# fm-radio.net
KiCad netlist of a schematic drawn in EAGLE
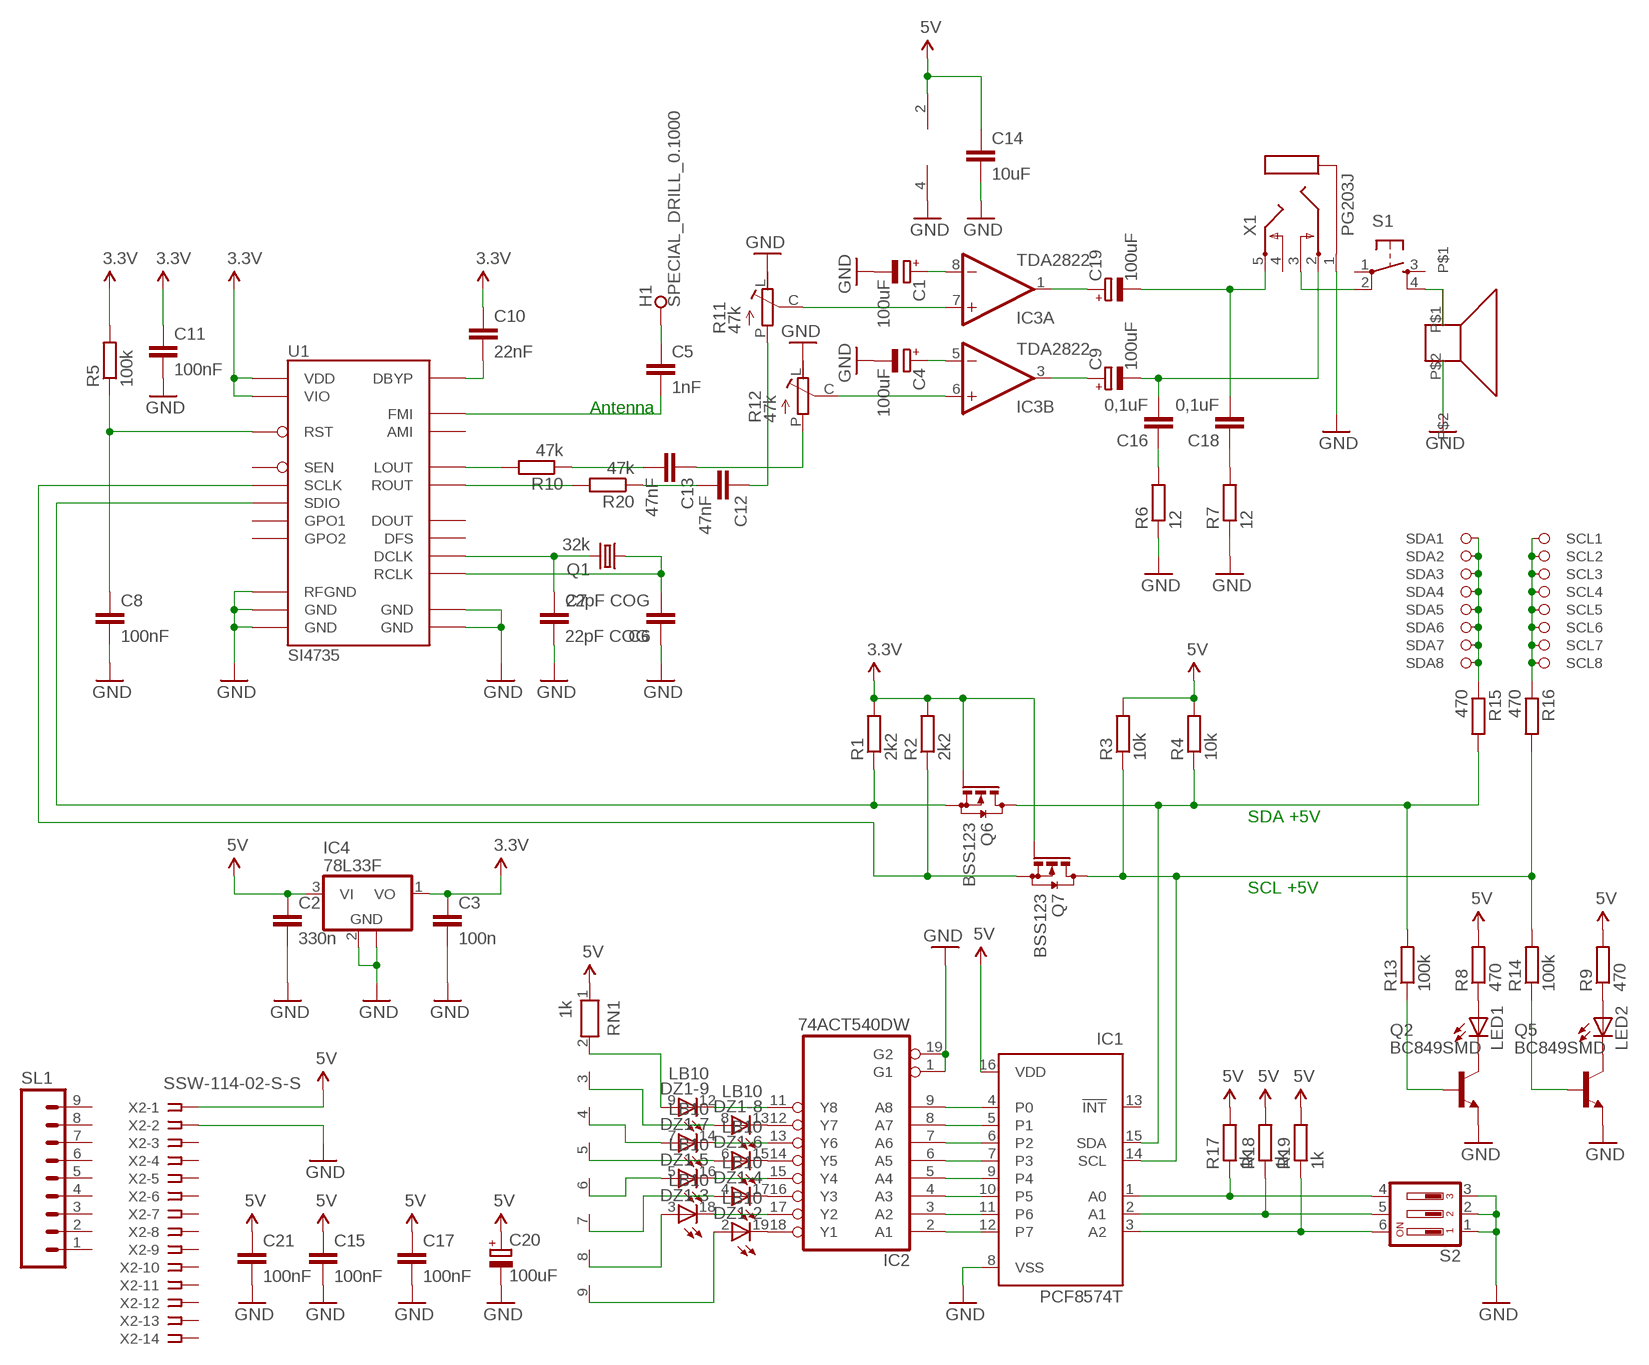
[diagram p0: schematic, sheet 1]

(export (version "E")
  (design (tool "Eeschema 10.0.6"))
  (components
    (comp (ref "C1")
      (value "100uF")
      (footprint "eagle-import:CT3528")
      (libsource (lib "eagle-import") (part "CPOL-EUCT3528"))
    )
    (comp (ref "C2")
      (value "330n")
      (footprint "eagle-import:C1206")
      (libsource (lib "eagle-import") (part "C-EUC1206"))
    )
    (comp (ref "C3")
      (value "100n")
      (footprint "eagle-import:C1206")
      (libsource (lib "eagle-import") (part "C-EUC1206"))
    )
    (comp (ref "C4")
      (value "100uF")
      (footprint "eagle-import:CT3528")
      (libsource (lib "eagle-import") (part "CPOL-EUCT3528"))
    )
    (comp (ref "C5")
      (value "1nF")
      (footprint "eagle-import:C1206")
      (libsource (lib "eagle-import") (part "C-EUC1206"))
    )
    (comp (ref "C6")
      (value "22pF COG")
      (footprint "eagle-import:C1206")
      (libsource (lib "eagle-import") (part "C-EUC1206"))
    )
    (comp (ref "C7")
      (value "22pF COG")
      (footprint "eagle-import:C1206")
      (libsource (lib "eagle-import") (part "C-EUC1206"))
    )
    (comp (ref "C8")
      (value "100nF")
      (footprint "eagle-import:C1206")
      (libsource (lib "eagle-import") (part "C-EUC1206"))
    )
    (comp (ref "C9")
      (value "100uF")
      (footprint "eagle-import:CT3528")
      (libsource (lib "eagle-import") (part "CPOL-EUCT3528"))
    )
    (comp (ref "C10")
      (value "22nF")
      (footprint "eagle-import:C1206")
      (libsource (lib "eagle-import") (part "C-EUC1206"))
    )
    (comp (ref "C11")
      (value "100nF")
      (footprint "eagle-import:C1206")
      (libsource (lib "eagle-import") (part "C-EUC1206"))
    )
    (comp (ref "C12")
      (value "47nF")
      (footprint "eagle-import:C1206")
      (libsource (lib "eagle-import") (part "C-EUC1206"))
    )
    (comp (ref "C13")
      (value "47nF")
      (footprint "eagle-import:C1206")
      (libsource (lib "eagle-import") (part "C-EUC1206"))
    )
    (comp (ref "C14")
      (value "10uF")
      (footprint "eagle-import:C1206")
      (libsource (lib "eagle-import") (part "C-EUC1206"))
    )
    (comp (ref "C15")
      (value "100nF")
      (footprint "eagle-import:C1206")
      (libsource (lib "eagle-import") (part "C-EUC1206"))
    )
    (comp (ref "C16")
      (value "0,1uF")
      (footprint "eagle-import:C1206")
      (libsource (lib "eagle-import") (part "C-EUC1206"))
    )
    (comp (ref "C17")
      (value "100nF")
      (footprint "eagle-import:C1206")
      (libsource (lib "eagle-import") (part "C-EUC1206"))
    )
    (comp (ref "C18")
      (value "0,1uF")
      (footprint "eagle-import:C1206")
      (libsource (lib "eagle-import") (part "C-EUC1206"))
    )
    (comp (ref "C19")
      (value "100uF")
      (footprint "eagle-import:CT3528")
      (libsource (lib "eagle-import") (part "CPOL-EUCT3528"))
    )
    (comp (ref "C20")
      (value "100uF")
      (footprint "eagle-import:CT3528")
      (libsource (lib "eagle-import") (part "CPOL-EUCT3528"))
    )
    (comp (ref "C21")
      (value "100nF")
      (footprint "eagle-import:C1206")
      (libsource (lib "eagle-import") (part "C-EUC1206"))
    )
    (comp (ref "DZ1")
      (value "LB10")
      (footprint "eagle-import:LB10")
      (libsource (lib "eagle-import") (part "LB10"))
    )
    (comp (ref "H1")
      (value "SPECIAL_DRILL_0.1000")
      (footprint "eagle-import:PAD_0.1000")
      (libsource (lib "eagle-import") (part "SPECIAL_DRILL_0.1000"))
    )
    (comp (ref "IC1")
      (value "PCF8574T")
      (footprint "eagle-import:SO16W")
      (fields (field (name "MPN") "PCF8574T/3,512"))
      (libsource (lib "eagle-import") (part "PCF8574T"))
    )
    (comp (ref "IC2")
      (value "74ACT540DW")
      (footprint "eagle-import:SO20W")
      (libsource (lib "eagle-import") (part "74540DWACT"))
    )
    (comp (ref "IC3")
      (value "TDA2822")
      (footprint "eagle-import:SO08")
      (libsource (lib "eagle-import") (part "L272D"))
    )
    (comp (ref "IC4")
      (value "78L33F")
      (footprint "eagle-import:SOT89")
      (libsource (lib "eagle-import") (part "78LF05"))
    )
    (comp (ref "LED1")
      (value "LEDCHIPLED_1206")
      (footprint "eagle-import:CHIPLED_1206")
      (libsource (lib "eagle-import") (part "LEDCHIPLED_1206"))
    )
    (comp (ref "LED2")
      (value "LEDCHIPLED_1206")
      (footprint "eagle-import:CHIPLED_1206")
      (libsource (lib "eagle-import") (part "LEDCHIPLED_1206"))
    )
    (comp (ref "Q1")
      (value "32k")
      (footprint "eagle-import:MC-306")
      (fields (field (name "MPN") "MC-306 60.0KHZ  100PPM ,12.5PF"))
      (libsource (lib "eagle-import") (part "MC-306"))
    )
    (comp (ref "Q2")
      (value "BC849SMD")
      (footprint "eagle-import:SOT23-BEC")
      (libsource (lib "eagle-import") (part "BC849SMD"))
    )
    (comp (ref "Q5")
      (value "BC849SMD")
      (footprint "eagle-import:SOT23-BEC")
      (libsource (lib "eagle-import") (part "BC849SMD"))
    )
    (comp (ref "Q6")
      (value "BSS123")
      (footprint "eagle-import:SOT23")
      (libsource (lib "eagle-import") (part "BSS123"))
    )
    (comp (ref "Q7")
      (value "BSS123")
      (footprint "eagle-import:SOT23")
      (libsource (lib "eagle-import") (part "BSS123"))
    )
    (comp (ref "R1")
      (value "2k2")
      (footprint "eagle-import:R1206")
      (libsource (lib "eagle-import") (part "R-EU_R1206"))
    )
    (comp (ref "R2")
      (value "2k2")
      (footprint "eagle-import:R1206")
      (libsource (lib "eagle-import") (part "R-EU_R1206"))
    )
    (comp (ref "R3")
      (value "10k")
      (footprint "eagle-import:R1206")
      (libsource (lib "eagle-import") (part "R-EU_R1206"))
    )
    (comp (ref "R4")
      (value "10k")
      (footprint "eagle-import:R1206")
      (libsource (lib "eagle-import") (part "R-EU_R1206"))
    )
    (comp (ref "R5")
      (value "100k")
      (footprint "eagle-import:R1206")
      (libsource (lib "eagle-import") (part "R-EU_R1206"))
    )
    (comp (ref "R6")
      (value "12")
      (footprint "eagle-import:R1206")
      (libsource (lib "eagle-import") (part "R-EU_R1206"))
    )
    (comp (ref "R7")
      (value "12")
      (footprint "eagle-import:R1206")
      (libsource (lib "eagle-import") (part "R-EU_R1206"))
    )
    (comp (ref "R8")
      (value "470")
      (footprint "eagle-import:R1206")
      (libsource (lib "eagle-import") (part "R-EU_R1206"))
    )
    (comp (ref "R9")
      (value "470")
      (footprint "eagle-import:R1206")
      (libsource (lib "eagle-import") (part "R-EU_R1206"))
    )
    (comp (ref "R10")
      (value "47k")
      (footprint "eagle-import:R1206")
      (libsource (lib "eagle-import") (part "R-EU_R1206"))
    )
    (comp (ref "R11")
      (value "47k")
      (footprint "eagle-import:TRIMER")
      (libsource (lib "eagle-import") (part "TRIMER"))
    )
    (comp (ref "R12")
      (value "47k")
      (footprint "eagle-import:TRIMER")
      (libsource (lib "eagle-import") (part "TRIMER"))
    )
    (comp (ref "R13")
      (value "100k")
      (footprint "eagle-import:R1206")
      (libsource (lib "eagle-import") (part "R-EU_R1206"))
    )
    (comp (ref "R14")
      (value "100k")
      (footprint "eagle-import:R1206")
      (libsource (lib "eagle-import") (part "R-EU_R1206"))
    )
    (comp (ref "R15")
      (value "470")
      (footprint "eagle-import:R1206")
      (libsource (lib "eagle-import") (part "R-EU_R1206"))
    )
    (comp (ref "R16")
      (value "470")
      (footprint "eagle-import:R1206")
      (libsource (lib "eagle-import") (part "R-EU_R1206"))
    )
    (comp (ref "R17")
      (value "1k")
      (footprint "eagle-import:R1206")
      (libsource (lib "eagle-import") (part "R-EU_R1206"))
    )
    (comp (ref "R18")
      (value "1k")
      (footprint "eagle-import:R1206")
      (libsource (lib "eagle-import") (part "R-EU_R1206"))
    )
    (comp (ref "R19")
      (value "1k")
      (footprint "eagle-import:R1206")
      (libsource (lib "eagle-import") (part "R-EU_R1206"))
    )
    (comp (ref "R20")
      (value "47k")
      (footprint "eagle-import:R1206")
      (libsource (lib "eagle-import") (part "R-EU_R1206"))
    )
    (comp (ref "RN1")
      (value "1k")
      (footprint "eagle-import:RN-9")
      (libsource (lib "eagle-import") (part "RN08"))
    )
    (comp (ref "S1")
      (value "TAC_SWITCHPTH")
      (footprint "eagle-import:TACTILE-PTH")
      (libsource (lib "eagle-import") (part "TAC_SWITCHPTH"))
    )
    (comp (ref "S2")
      (value "DIP03YL")
      (footprint "eagle-import:DIP03YL")
      (libsource (lib "eagle-import") (part "DIP03YL"))
    )
    (comp (ref "SL1")
      (value "M09")
      (footprint "eagle-import:09P")
      (libsource (lib "eagle-import") (part "M09"))
    )
    (comp (ref "U$1")
      (value "K23PC")
      (footprint "eagle-import:K23PC")
      (libsource (lib "eagle-import") (part "K23PC"))
    )
    (comp (ref "U$7")
      (value "PATICE_I2C")
      (footprint "eagle-import:PATICE_I2C")
      (libsource (lib "eagle-import") (part "PATICE_I2C"))
    )
    (comp (ref "U1")
      (value "SI4735")
      (footprint "eagle-import:SSOP24_NARROW")
      (libsource (lib "eagle-import") (part "SI4735"))
    )
    (comp (ref "X1")
      (value "PG203J")
      (footprint "eagle-import:PG203J")
      (libsource (lib "eagle-import") (part "PG203J"))
    )
    (comp (ref "X2")
      (value "SSW-114-02-S-S")
      (footprint "eagle-import:SSW-114-02-S-S")
      (libsource (lib "eagle-import") (part "SSW-114-02-S-S"))
    )
  )
  (nets
    (net (code "1") (name "3.3V") (class "Default")
      (node (ref "C10") (pin "1") (pinfunction "1_1") (pintype "passive"))
      (node (ref "C11") (pin "1") (pinfunction "1_1") (pintype "passive"))
      (node (ref "C3") (pin "1") (pinfunction "1_1") (pintype "passive"))
      (node (ref "IC4") (pin "1") (pinfunction "VO_1") (pintype "passive"))
      (node (ref "Q6") (pin "1") (pinfunction "G_1") (pintype "passive"))
      (node (ref "Q7") (pin "1") (pinfunction "G_1") (pintype "passive"))
      (node (ref "R1") (pin "2") (pinfunction "2_2") (pintype "passive"))
      (node (ref "R2") (pin "2") (pinfunction "2_2") (pintype "passive"))
      (node (ref "R5") (pin "2") (pinfunction "2_2") (pintype "passive"))
      (node (ref "U1") (pin "20") (pinfunction "VIO_20") (pintype "bidirectional"))
      (node (ref "U1") (pin "21") (pinfunction "VDD_21") (pintype "bidirectional"))
    )
    (net (code "2") (name "5V") (class "Default")
      (node (ref "C14") (pin "1") (pinfunction "1_1") (pintype "passive"))
      (node (ref "C15") (pin "1") (pinfunction "1_1") (pintype "passive"))
      (node (ref "C17") (pin "1") (pinfunction "1_1") (pintype "passive"))
      (node (ref "C2") (pin "1") (pinfunction "1_1") (pintype "passive"))
      (node (ref "C20") (pin "+") (pinfunction "+_+") (pintype "passive"))
      (node (ref "C21") (pin "1") (pinfunction "1_1") (pintype "passive"))
      (node (ref "IC1") (pin "16") (pinfunction "VDD_16") (pintype "power_in"))
      (node (ref "IC3") (pin "2") (pinfunction "V+_2") (pintype "power_in"))
      (node (ref "IC4") (pin "3") (pinfunction "VI_3") (pintype "input"))
      (node (ref "R17") (pin "2") (pinfunction "2_2") (pintype "passive"))
      (node (ref "R18") (pin "2") (pinfunction "2_2") (pintype "passive"))
      (node (ref "R19") (pin "2") (pinfunction "2_2") (pintype "passive"))
      (node (ref "R3") (pin "2") (pinfunction "2_2") (pintype "passive"))
      (node (ref "R4") (pin "2") (pinfunction "2_2") (pintype "passive"))
      (node (ref "R8") (pin "2") (pinfunction "2_2") (pintype "passive"))
      (node (ref "R9") (pin "2") (pinfunction "2_2") (pintype "passive"))
      (node (ref "RN1") (pin "1") (pinfunction "1_1") (pintype "passive"))
      (node (ref "X2") (pin "1") (pinfunction "1_1") (pintype "passive"))
    )
    (net (code "3") (name "GND") (class "Default")
      (node (ref "C1") (pin "-") (pinfunction "-_-") (pintype "passive"))
      (node (ref "C11") (pin "2") (pinfunction "2_2") (pintype "passive"))
      (node (ref "C14") (pin "2") (pinfunction "2_2") (pintype "passive"))
      (node (ref "C15") (pin "2") (pinfunction "2_2") (pintype "passive"))
      (node (ref "C17") (pin "2") (pinfunction "2_2") (pintype "passive"))
      (node (ref "C2") (pin "2") (pinfunction "2_2") (pintype "passive"))
      (node (ref "C20") (pin "-") (pinfunction "-_-") (pintype "passive"))
      (node (ref "C21") (pin "2") (pinfunction "2_2") (pintype "passive"))
      (node (ref "C3") (pin "2") (pinfunction "2_2") (pintype "passive"))
      (node (ref "C4") (pin "-") (pinfunction "-_-") (pintype "passive"))
      (node (ref "C6") (pin "1") (pinfunction "1_1") (pintype "passive"))
      (node (ref "C7") (pin "2") (pinfunction "2_2") (pintype "passive"))
      (node (ref "C8") (pin "2") (pinfunction "2_2") (pintype "passive"))
      (node (ref "IC1") (pin "8") (pinfunction "VSS_8") (pintype "power_in"))
      (node (ref "IC2") (pin "1") (pinfunction "G1_1") (pintype "input"))
      (node (ref "IC2") (pin "19") (pinfunction "G2_19") (pintype "input"))
      (node (ref "IC3") (pin "4") (pinfunction "GND_4") (pintype "power_in"))
      (node (ref "IC4") (pin "2") (pinfunction "GND_2") (pintype "passive"))
      (node (ref "IC4") (pin "2@1") (pinfunction "GND_2@1") (pintype "passive"))
      (node (ref "Q2") (pin "E") (pinfunction "E_E") (pintype "passive"))
      (node (ref "Q5") (pin "E") (pinfunction "E_E") (pintype "passive"))
      (node (ref "R11") (pin "L") (pinfunction "L_L") (pintype "passive"))
      (node (ref "R12") (pin "L") (pinfunction "L_L") (pintype "passive"))
      (node (ref "R6") (pin "1") (pinfunction "1_1") (pintype "passive"))
      (node (ref "R7") (pin "1") (pinfunction "1_1") (pintype "passive"))
      (node (ref "S2") (pin "1") (pinfunction "1_1") (pintype "passive"))
      (node (ref "S2") (pin "2") (pinfunction "2_2") (pintype "passive"))
      (node (ref "S2") (pin "3") (pinfunction "3_3") (pintype "passive"))
      (node (ref "U$1") (pin "P$2") (pinfunction "P$2_P$2") (pintype "bidirectional"))
      (node (ref "U1") (pin "10") (pinfunction "GND_10") (pintype "bidirectional"))
      (node (ref "U1") (pin "11") (pinfunction "GND_11") (pintype "bidirectional"))
      (node (ref "U1") (pin "13") (pinfunction "GND_13") (pintype "bidirectional"))
      (node (ref "U1") (pin "14") (pinfunction "GND_14") (pintype "bidirectional"))
      (node (ref "U1") (pin "9") (pinfunction "RFGND_9") (pintype "bidirectional"))
      (node (ref "X1") (pin "1") (pinfunction "1_1") (pintype "passive"))
      (node (ref "X2") (pin "2") (pinfunction "1_2") (pintype "passive"))
    )
    (net (code "4") (name "Net-(C5-Pad1)") (class "Default")
      (node (ref "C5") (pin "1") (pinfunction "1_1") (pintype "passive"))
      (node (ref "H1") (pin "1") (pinfunction "1_1") (pintype "passive"))
    )
    (net (code "5") (name "Net-(C12-Pad1)") (class "Default")
      (node (ref "C12") (pin "1") (pinfunction "1_1") (pintype "passive"))
      (node (ref "R11") (pin "P") (pinfunction "P_P") (pintype "passive"))
    )
    (net (code "6") (name "Net-(C12-Pad2)") (class "Default")
      (node (ref "C12") (pin "2") (pinfunction "2_2") (pintype "passive"))
      (node (ref "R20") (pin "1") (pinfunction "1_1") (pintype "passive"))
    )
    (net (code "7") (name "Net-(C13-Pad1)") (class "Default")
      (node (ref "C13") (pin "1") (pinfunction "1_1") (pintype "passive"))
      (node (ref "R12") (pin "P") (pinfunction "P_P") (pintype "passive"))
    )
    (net (code "8") (name "Net-(C13-Pad2)") (class "Default")
      (node (ref "C13") (pin "2") (pinfunction "2_2") (pintype "passive"))
      (node (ref "R10") (pin "1") (pinfunction "1_1") (pintype "passive"))
    )
    (net (code "9") (name "Net-(C16-Pad1)") (class "Default")
      (node (ref "C16") (pin "1") (pinfunction "1_1") (pintype "passive"))
      (node (ref "R6") (pin "2") (pinfunction "2_2") (pintype "passive"))
    )
    (net (code "10") (name "Net-(C16-Pad2)") (class "Default")
      (node (ref "C16") (pin "2") (pinfunction "2_2") (pintype "passive"))
      (node (ref "C9") (pin "-") (pinfunction "-_-") (pintype "passive"))
      (node (ref "X1") (pin "2") (pinfunction "2_2") (pintype "passive"))
    )
    (net (code "11") (name "Net-(C18-Pad1)") (class "Default")
      (node (ref "C18") (pin "1") (pinfunction "1_1") (pintype "passive"))
      (node (ref "R7") (pin "2") (pinfunction "2_2") (pintype "passive"))
    )
    (net (code "12") (name "Net-(C18-Pad2)") (class "Default")
      (node (ref "C18") (pin "2") (pinfunction "2_2") (pintype "passive"))
      (node (ref "C19") (pin "-") (pinfunction "-_-") (pintype "passive"))
      (node (ref "X1") (pin "5") (pinfunction "5_5") (pintype "passive"))
    )
    (net (code "13") (name "Net-(DZ1C-A)") (class "Default")
      (node (ref "DZ1") (pin "2") (pinfunction "A_2") (pintype "passive"))
      (node (ref "RN1") (pin "9") (pinfunction "9_9") (pintype "passive"))
    )
    (net (code "14") (name "Net-(DZ1C-C)") (class "Default")
      (node (ref "DZ1") (pin "19") (pinfunction "C_19") (pintype "passive"))
      (node (ref "IC2") (pin "18") (pinfunction "Y1_18") (pintype "tri_state"))
    )
    (net (code "15") (name "Net-(DZ1D-A)") (class "Default")
      (node (ref "DZ1") (pin "3") (pinfunction "A_3") (pintype "passive"))
      (node (ref "RN1") (pin "8") (pinfunction "8_8") (pintype "passive"))
    )
    (net (code "16") (name "Net-(DZ1D-C)") (class "Default")
      (node (ref "DZ1") (pin "18") (pinfunction "C_18") (pintype "passive"))
      (node (ref "IC2") (pin "17") (pinfunction "Y2_17") (pintype "tri_state"))
    )
    (net (code "17") (name "Net-(DZ1E-A)") (class "Default")
      (node (ref "DZ1") (pin "4") (pinfunction "A_4") (pintype "passive"))
      (node (ref "RN1") (pin "7") (pinfunction "7_7") (pintype "passive"))
    )
    (net (code "18") (name "Net-(DZ1E-C)") (class "Default")
      (node (ref "DZ1") (pin "17") (pinfunction "C_17") (pintype "passive"))
      (node (ref "IC2") (pin "16") (pinfunction "Y3_16") (pintype "tri_state"))
    )
    (net (code "19") (name "Net-(DZ1F-A)") (class "Default")
      (node (ref "DZ1") (pin "5") (pinfunction "A_5") (pintype "passive"))
      (node (ref "RN1") (pin "6") (pinfunction "6_6") (pintype "passive"))
    )
    (net (code "20") (name "Net-(DZ1F-C)") (class "Default")
      (node (ref "DZ1") (pin "16") (pinfunction "C_16") (pintype "passive"))
      (node (ref "IC2") (pin "15") (pinfunction "Y4_15") (pintype "tri_state"))
    )
    (net (code "21") (name "Net-(DZ1G-A)") (class "Default")
      (node (ref "DZ1") (pin "6") (pinfunction "A_6") (pintype "passive"))
      (node (ref "RN1") (pin "5") (pinfunction "5_5") (pintype "passive"))
    )
    (net (code "22") (name "Net-(DZ1G-C)") (class "Default")
      (node (ref "DZ1") (pin "15") (pinfunction "C_15") (pintype "passive"))
      (node (ref "IC2") (pin "14") (pinfunction "Y5_14") (pintype "tri_state"))
    )
    (net (code "23") (name "Net-(DZ1H-A)") (class "Default")
      (node (ref "DZ1") (pin "7") (pinfunction "A_7") (pintype "passive"))
      (node (ref "RN1") (pin "4") (pinfunction "4_4") (pintype "passive"))
    )
    (net (code "24") (name "Net-(DZ1H-C)") (class "Default")
      (node (ref "DZ1") (pin "14") (pinfunction "C_14") (pintype "passive"))
      (node (ref "IC2") (pin "13") (pinfunction "Y6_13") (pintype "tri_state"))
    )
    (net (code "25") (name "Net-(DZ1I-A)") (class "Default")
      (node (ref "DZ1") (pin "8") (pinfunction "A_8") (pintype "passive"))
      (node (ref "RN1") (pin "3") (pinfunction "3_3") (pintype "passive"))
    )
    (net (code "26") (name "Net-(DZ1I-C)") (class "Default")
      (node (ref "DZ1") (pin "13") (pinfunction "C_13") (pintype "passive"))
      (node (ref "IC2") (pin "12") (pinfunction "Y7_12") (pintype "tri_state"))
    )
    (net (code "27") (name "Net-(DZ1J-A)") (class "Default")
      (node (ref "DZ1") (pin "9") (pinfunction "A_9") (pintype "passive"))
      (node (ref "RN1") (pin "2") (pinfunction "2_2") (pintype "passive"))
    )
    (net (code "28") (name "Net-(DZ1J-C)") (class "Default")
      (node (ref "DZ1") (pin "12") (pinfunction "C_12") (pintype "passive"))
      (node (ref "IC2") (pin "11") (pinfunction "Y8_11") (pintype "tri_state"))
    )
    (net (code "29") (name "Net-(IC1-A0)") (class "Default")
      (node (ref "IC1") (pin "1") (pinfunction "A0_1") (pintype "input"))
      (node (ref "R17") (pin "1") (pinfunction "1_1") (pintype "passive"))
      (node (ref "S2") (pin "4") (pinfunction "4_4") (pintype "passive"))
    )
    (net (code "30") (name "Net-(IC1-A1)") (class "Default")
      (node (ref "IC1") (pin "2") (pinfunction "A1_2") (pintype "input"))
      (node (ref "R18") (pin "1") (pinfunction "1_1") (pintype "passive"))
      (node (ref "S2") (pin "5") (pinfunction "5_5") (pintype "passive"))
    )
    (net (code "31") (name "Net-(IC1-A2)") (class "Default")
      (node (ref "IC1") (pin "3") (pinfunction "A2_3") (pintype "input"))
      (node (ref "R19") (pin "1") (pinfunction "1_1") (pintype "passive"))
      (node (ref "S2") (pin "6") (pinfunction "6_6") (pintype "passive"))
    )
    (net (code "32") (name "Net-(IC1-P0)") (class "Default")
      (node (ref "IC1") (pin "4") (pinfunction "P0_4") (pintype "bidirectional"))
      (node (ref "IC2") (pin "9") (pinfunction "A8_9") (pintype "input"))
    )
    (net (code "33") (name "Net-(IC1-P1)") (class "Default")
      (node (ref "IC1") (pin "5") (pinfunction "P1_5") (pintype "bidirectional"))
      (node (ref "IC2") (pin "8") (pinfunction "A7_8") (pintype "input"))
    )
    (net (code "34") (name "Net-(IC1-P2)") (class "Default")
      (node (ref "IC1") (pin "6") (pinfunction "P2_6") (pintype "bidirectional"))
      (node (ref "IC2") (pin "7") (pinfunction "A6_7") (pintype "input"))
    )
    (net (code "35") (name "Net-(IC1-P3)") (class "Default")
      (node (ref "IC1") (pin "7") (pinfunction "P3_7") (pintype "bidirectional"))
      (node (ref "IC2") (pin "6") (pinfunction "A5_6") (pintype "input"))
    )
    (net (code "36") (name "Net-(IC1-P4)") (class "Default")
      (node (ref "IC1") (pin "9") (pinfunction "P4_9") (pintype "bidirectional"))
      (node (ref "IC2") (pin "5") (pinfunction "A4_5") (pintype "input"))
    )
    (net (code "37") (name "Net-(IC1-P5)") (class "Default")
      (node (ref "IC1") (pin "10") (pinfunction "P5_10") (pintype "bidirectional"))
      (node (ref "IC2") (pin "4") (pinfunction "A3_4") (pintype "input"))
    )
    (net (code "38") (name "Net-(IC1-P6)") (class "Default")
      (node (ref "IC1") (pin "11") (pinfunction "P6_11") (pintype "bidirectional"))
      (node (ref "IC2") (pin "3") (pinfunction "A2_3") (pintype "input"))
    )
    (net (code "39") (name "Net-(IC1-P7)") (class "Default")
      (node (ref "IC1") (pin "12") (pinfunction "P7_12") (pintype "bidirectional"))
      (node (ref "IC2") (pin "2") (pinfunction "A1_2") (pintype "input"))
    )
    (net (code "40") (name "Net-(IC1-SCL)") (class "Default")
      (node (ref "IC1") (pin "14") (pinfunction "SCL_14") (pintype "input"))
      (node (ref "Q7") (pin "3") (pinfunction "D_3") (pintype "passive"))
      (node (ref "R14") (pin "2") (pinfunction "2_2") (pintype "passive"))
      (node (ref "R16") (pin "2") (pinfunction "2_2") (pintype "passive"))
      (node (ref "R3") (pin "1") (pinfunction "1_1") (pintype "passive"))
    )
    (net (code "41") (name "Net-(IC1-SDA)") (class "Default")
      (node (ref "IC1") (pin "15") (pinfunction "SDA_15") (pintype "bidirectional"))
      (node (ref "Q6") (pin "3") (pinfunction "D_3") (pintype "passive"))
      (node (ref "R13") (pin "2") (pinfunction "2_2") (pintype "passive"))
      (node (ref "R15") (pin "2") (pinfunction "2_2") (pintype "passive"))
      (node (ref "R4") (pin "1") (pinfunction "1_1") (pintype "passive"))
    )
    (net (code "42") (name "Net-(IC3A-+IN)") (class "Default")
      (node (ref "IC3") (pin "7") (pinfunction "+IN_7") (pintype "input"))
      (node (ref "R11") (pin "C") (pinfunction "C_C") (pintype "passive"))
    )
    (net (code "43") (name "Net-(IC3A--IN)") (class "Default")
      (node (ref "C1") (pin "+") (pinfunction "+_+") (pintype "passive"))
      (node (ref "IC3") (pin "8") (pinfunction "-IN_8") (pintype "input"))
    )
    (net (code "44") (name "Net-(IC3A-OUT)") (class "Default")
      (node (ref "C19") (pin "+") (pinfunction "+_+") (pintype "passive"))
      (node (ref "IC3") (pin "1") (pinfunction "OUT_1") (pintype "output"))
    )
    (net (code "45") (name "Net-(IC3B-+IN)") (class "Default")
      (node (ref "IC3") (pin "6") (pinfunction "+IN_6") (pintype "input"))
      (node (ref "R12") (pin "C") (pinfunction "C_C") (pintype "passive"))
    )
    (net (code "46") (name "Net-(IC3B--IN)") (class "Default")
      (node (ref "C4") (pin "+") (pinfunction "+_+") (pintype "passive"))
      (node (ref "IC3") (pin "5") (pinfunction "-IN_5") (pintype "input"))
    )
    (net (code "47") (name "Net-(IC3B-OUT)") (class "Default")
      (node (ref "C9") (pin "+") (pinfunction "+_+") (pintype "passive"))
      (node (ref "IC3") (pin "3") (pinfunction "OUT_3") (pintype "output"))
    )
    (net (code "48") (name "Net-(LED1-PadA)") (class "Default")
      (node (ref "LED1") (pin "A") (pinfunction "A_A") (pintype "passive"))
      (node (ref "R8") (pin "1") (pinfunction "1_1") (pintype "passive"))
    )
    (net (code "49") (name "Net-(LED1-PadC)") (class "Default")
      (node (ref "LED1") (pin "C") (pinfunction "C_C") (pintype "passive"))
      (node (ref "Q2") (pin "C") (pinfunction "C_C") (pintype "passive"))
    )
    (net (code "50") (name "Net-(LED2-PadA)") (class "Default")
      (node (ref "LED2") (pin "A") (pinfunction "A_A") (pintype "passive"))
      (node (ref "R9") (pin "1") (pinfunction "1_1") (pintype "passive"))
    )
    (net (code "51") (name "Net-(LED2-PadC)") (class "Default")
      (node (ref "LED2") (pin "C") (pinfunction "C_C") (pintype "passive"))
      (node (ref "Q5") (pin "C") (pinfunction "C_C") (pintype "passive"))
    )
    (net (code "52") (name "Net-(Q1-2)") (class "Default")
      (node (ref "C7") (pin "1") (pinfunction "1_1") (pintype "passive"))
      (node (ref "Q1") (pin "4") (pinfunction "2_4") (pintype "passive"))
      (node (ref "U1") (pin "3") (pinfunction "DCLK_3") (pintype "bidirectional"))
    )
    (net (code "53") (name "Net-(Q2-PadB)") (class "Default")
      (node (ref "Q2") (pin "B") (pinfunction "B_B") (pintype "passive"))
      (node (ref "R13") (pin "1") (pinfunction "1_1") (pintype "passive"))
    )
    (net (code "54") (name "Net-(Q5-PadB)") (class "Default")
      (node (ref "Q5") (pin "B") (pinfunction "B_B") (pintype "passive"))
      (node (ref "R14") (pin "1") (pinfunction "1_1") (pintype "passive"))
    )
    (net (code "55") (name "Net-(Q6-S)") (class "Default")
      (node (ref "Q6") (pin "2") (pinfunction "S_2") (pintype "passive"))
      (node (ref "R1") (pin "1") (pinfunction "1_1") (pintype "passive"))
      (node (ref "U1") (pin "18") (pinfunction "SDIO_18") (pintype "bidirectional"))
    )
    (net (code "56") (name "Net-(Q7-S)") (class "Default")
      (node (ref "Q7") (pin "2") (pinfunction "S_2") (pintype "passive"))
      (node (ref "R2") (pin "1") (pinfunction "1_1") (pintype "passive"))
      (node (ref "U1") (pin "17") (pinfunction "SCLK_17") (pintype "bidirectional"))
    )
    (net (code "57") (name "Net-(S1-Pad2)") (class "Default")
      (node (ref "S1") (pin "2") (pinfunction "2_2") (pintype "passive"))
      (node (ref "X1") (pin "3") (pinfunction "3_3") (pintype "passive"))
    )
    (net (code "58") (name "Net-(S1-Pad4)") (class "Default")
      (node (ref "S1") (pin "4") (pinfunction "4_4") (pintype "passive"))
      (node (ref "U$1") (pin "P$1") (pinfunction "P$1_P$1") (pintype "bidirectional"))
    )
    (net (code "59") (name "Net-(U$7A-SCL1)") (class "Default")
      (node (ref "R16") (pin "1") (pinfunction "1_1") (pintype "passive"))
      (node (ref "U$7") (pin "SCL_1") (pinfunction "SCL1_SCL_1") (pintype "bidirectional"))
      (node (ref "U$7") (pin "SCL_2") (pinfunction "SCL2_SCL_2") (pintype "bidirectional"))
      (node (ref "U$7") (pin "SCL_3") (pinfunction "SCL3_SCL_3") (pintype "bidirectional"))
      (node (ref "U$7") (pin "SCL_4") (pinfunction "SCL4_SCL_4") (pintype "bidirectional"))
      (node (ref "U$7") (pin "SCL_5") (pinfunction "SCL5_SCL_5") (pintype "bidirectional"))
      (node (ref "U$7") (pin "SCL_6") (pinfunction "SCL6_SCL_6") (pintype "bidirectional"))
      (node (ref "U$7") (pin "SCL_7") (pinfunction "SCL7_SCL_7") (pintype "bidirectional"))
      (node (ref "U$7") (pin "SCL_8") (pinfunction "SCL8_SCL_8") (pintype "bidirectional"))
    )
    (net (code "60") (name "Net-(U$7B-SDA1)") (class "Default")
      (node (ref "R15") (pin "1") (pinfunction "1_1") (pintype "passive"))
      (node (ref "U$7") (pin "SDA_1") (pinfunction "SDA1_SDA_1") (pintype "bidirectional"))
      (node (ref "U$7") (pin "SDA_2") (pinfunction "SDA2_SDA_2") (pintype "bidirectional"))
      (node (ref "U$7") (pin "SDA_3") (pinfunction "SDA3_SDA_3") (pintype "bidirectional"))
      (node (ref "U$7") (pin "SDA_4") (pinfunction "SDA4_SDA_4") (pintype "bidirectional"))
      (node (ref "U$7") (pin "SDA_5") (pinfunction "SDA5_SDA_5") (pintype "bidirectional"))
      (node (ref "U$7") (pin "SDA_6") (pinfunction "SDA6_SDA_6") (pintype "bidirectional"))
      (node (ref "U$7") (pin "SDA_7") (pinfunction "SDA7_SDA_7") (pintype "bidirectional"))
      (node (ref "U$7") (pin "SDA_8") (pinfunction "SDA8_SDA_8") (pintype "bidirectional"))
    )
    (net (code "61") (name "Net-(U1-DBYP)") (class "Default")
      (node (ref "C10") (pin "2") (pinfunction "2_2") (pintype "passive"))
      (node (ref "U1") (pin "22") (pinfunction "DBYP_22") (pintype "bidirectional"))
    )
    (net (code "62") (name "Net-(U1-FMI)") (class "Default")
      (node (ref "C5") (pin "2") (pinfunction "2_2") (pintype "passive"))
      (node (ref "U1") (pin "8") (pinfunction "FMI_8") (pintype "bidirectional"))
    )
    (net (code "63") (name "Net-(U1-LOUT)") (class "Default")
      (node (ref "R10") (pin "2") (pinfunction "2_2") (pintype "passive"))
      (node (ref "U1") (pin "24") (pinfunction "LOUT_24") (pintype "bidirectional"))
    )
    (net (code "64") (name "Net-(U1-RCLK)") (class "Default")
      (node (ref "C6") (pin "2") (pinfunction "2_2") (pintype "passive"))
      (node (ref "Q1") (pin "1") (pinfunction "1_1") (pintype "passive"))
      (node (ref "U1") (pin "19") (pinfunction "RCLK_19") (pintype "bidirectional"))
    )
    (net (code "65") (name "Net-(U1-ROUT)") (class "Default")
      (node (ref "R20") (pin "2") (pinfunction "2_2") (pintype "passive"))
      (node (ref "U1") (pin "23") (pinfunction "ROUT_23") (pintype "bidirectional"))
    )
    (net (code "66") (name "Net-(U1-RST)") (class "Default")
      (node (ref "C8") (pin "1") (pinfunction "1_1") (pintype "passive"))
      (node (ref "R5") (pin "1") (pinfunction "1_1") (pintype "passive"))
      (node (ref "U1") (pin "15") (pinfunction "RST_15") (pintype "bidirectional"))
    )
    (net (code "67") (name "unconnected-(IC1-~{INT}-Pad13)") (class "Default")
      (node (ref "IC1") (pin "13") (pinfunction "~{INT}_13") (pintype "output"))
    )
    (net (code "68") (name "unconnected-(S1-Pad1)") (class "Default")
      (node (ref "S1") (pin "1") (pinfunction "1_1") (pintype "passive"))
    )
    (net (code "69") (name "unconnected-(S1-Pad3)") (class "Default")
      (node (ref "S1") (pin "3") (pinfunction "3_3") (pintype "passive"))
    )
    (net (code "70") (name "unconnected-(SL1-Pad1)") (class "Default")
      (node (ref "SL1") (pin "1") (pinfunction "1_1") (pintype "passive"))
    )
    (net (code "71") (name "unconnected-(SL1-Pad2)") (class "Default")
      (node (ref "SL1") (pin "2") (pinfunction "2_2") (pintype "passive"))
    )
    (net (code "72") (name "unconnected-(SL1-Pad3)") (class "Default")
      (node (ref "SL1") (pin "3") (pinfunction "3_3") (pintype "passive"))
    )
    (net (code "73") (name "unconnected-(SL1-Pad4)") (class "Default")
      (node (ref "SL1") (pin "4") (pinfunction "4_4") (pintype "passive"))
    )
    (net (code "74") (name "unconnected-(SL1-Pad5)") (class "Default")
      (node (ref "SL1") (pin "5") (pinfunction "5_5") (pintype "passive"))
    )
    (net (code "75") (name "unconnected-(SL1-Pad6)") (class "Default")
      (node (ref "SL1") (pin "6") (pinfunction "6_6") (pintype "passive"))
    )
    (net (code "76") (name "unconnected-(SL1-Pad7)") (class "Default")
      (node (ref "SL1") (pin "7") (pinfunction "7_7") (pintype "passive"))
    )
    (net (code "77") (name "unconnected-(SL1-Pad8)") (class "Default")
      (node (ref "SL1") (pin "8") (pinfunction "8_8") (pintype "passive"))
    )
    (net (code "78") (name "unconnected-(SL1-Pad9)") (class "Default")
      (node (ref "SL1") (pin "9") (pinfunction "9_9") (pintype "passive"))
    )
    (net (code "79") (name "unconnected-(U1-AMI-Pad12)") (class "Default")
      (node (ref "U1") (pin "12") (pinfunction "AMI_12") (pintype "bidirectional"))
    )
    (net (code "80") (name "unconnected-(U1-DFS-Pad2)") (class "Default")
      (node (ref "U1") (pin "2") (pinfunction "DFS_2") (pintype "bidirectional"))
    )
    (net (code "81") (name "unconnected-(U1-DOUT-Pad1)") (class "Default")
      (node (ref "U1") (pin "1") (pinfunction "DOUT_1") (pintype "bidirectional"))
    )
    (net (code "82") (name "unconnected-(U1-GPO1-Pad5)") (class "Default")
      (node (ref "U1") (pin "5") (pinfunction "GPO1_5") (pintype "bidirectional"))
    )
    (net (code "83") (name "unconnected-(U1-GPO2-Pad4)") (class "Default")
      (node (ref "U1") (pin "4") (pinfunction "GPO2_4") (pintype "bidirectional"))
    )
    (net (code "84") (name "unconnected-(U1-SEN-Pad16)") (class "Default")
      (node (ref "U1") (pin "16") (pinfunction "SEN_16") (pintype "bidirectional"))
    )
    (net (code "85") (name "unconnected-(X1-Pad4)") (class "Default")
      (node (ref "X1") (pin "4") (pinfunction "4_4") (pintype "passive"))
    )
    (net (code "86") (name "unconnected-(X2B-1-Pad10)") (class "Default")
      (node (ref "X2") (pin "10") (pinfunction "1_10") (pintype "passive"))
    )
    (net (code "87") (name "unconnected-(X2C-1-Pad11)") (class "Default")
      (node (ref "X2") (pin "11") (pinfunction "1_11") (pintype "passive"))
    )
    (net (code "88") (name "unconnected-(X2D-1-Pad12)") (class "Default")
      (node (ref "X2") (pin "12") (pinfunction "1_12") (pintype "passive"))
    )
    (net (code "89") (name "unconnected-(X2E-1-Pad13)") (class "Default")
      (node (ref "X2") (pin "13") (pinfunction "1_13") (pintype "passive"))
    )
    (net (code "90") (name "unconnected-(X2F-1-Pad14)") (class "Default")
      (node (ref "X2") (pin "14") (pinfunction "1_14") (pintype "passive"))
    )
    (net (code "91") (name "unconnected-(X2H-1-Pad3)") (class "Default")
      (node (ref "X2") (pin "3") (pinfunction "1_3") (pintype "passive"))
    )
    (net (code "92") (name "unconnected-(X2I-1-Pad4)") (class "Default")
      (node (ref "X2") (pin "4") (pinfunction "1_4") (pintype "passive"))
    )
    (net (code "93") (name "unconnected-(X2J-1-Pad5)") (class "Default")
      (node (ref "X2") (pin "5") (pinfunction "1_5") (pintype "passive"))
    )
    (net (code "94") (name "unconnected-(X2K-1-Pad6)") (class "Default")
      (node (ref "X2") (pin "6") (pinfunction "1_6") (pintype "passive"))
    )
    (net (code "95") (name "unconnected-(X2L-1-Pad7)") (class "Default")
      (node (ref "X2") (pin "7") (pinfunction "1_7") (pintype "passive"))
    )
    (net (code "96") (name "unconnected-(X2M-1-Pad8)") (class "Default")
      (node (ref "X2") (pin "8") (pinfunction "1_8") (pintype "passive"))
    )
    (net (code "97") (name "unconnected-(X2N-1-Pad9)") (class "Default")
      (node (ref "X2") (pin "9") (pinfunction "1_9") (pintype "passive"))
    )
  )
)
